# 3V3-CAN-Unisolated.net
KiCad netlist of a schematic drawn in Altium Designer
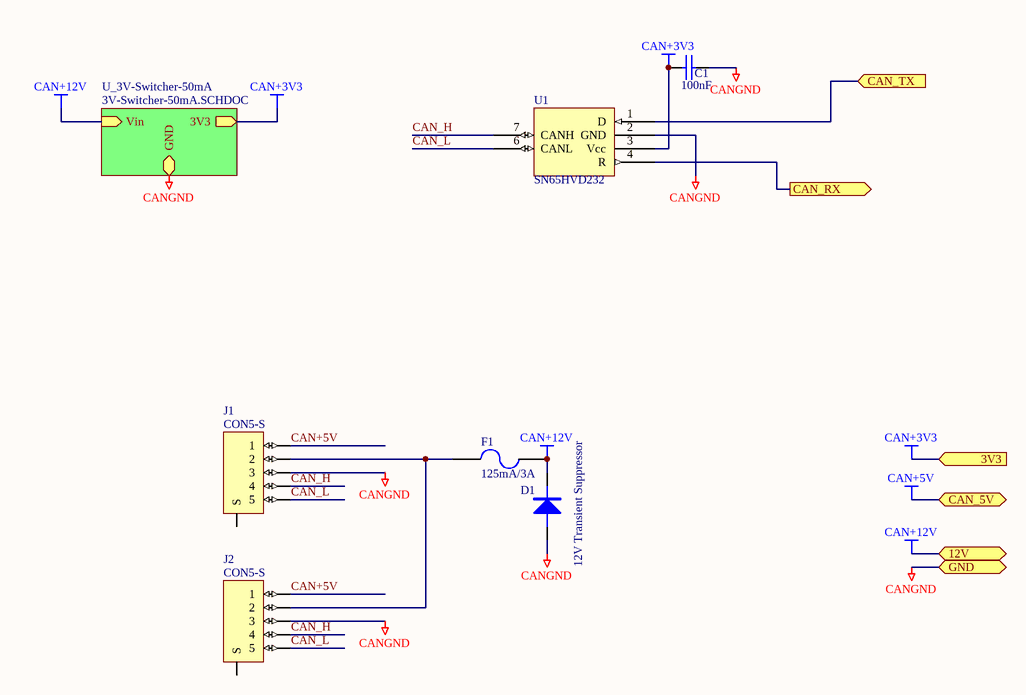
[diagram p0: 3V3-CAN-Unisolated.SchDoc]

(export (version "E")
  (design (tool "Eeschema 10.0.6"))
  (components
    (comp (ref "C1")
      (value "100nF")
      (footprint "0603")
      (description "Capacitor")
      (libsource (lib "*") (part "CAP"))
    )
    (comp (ref "D1")
      (value "12V Transient Suppressor")
      (footprint "SMA")
      (description "Diode")
      (libsource (lib "RCLDQ") (part "DIODE"))
    )
    (comp (ref "F1")
      (value "125mA/3A")
      (footprint "LITTELFUSE-154")
      (description "Fuse")
      (libsource (lib "*") (part "FUSE2"))
    )
    (comp (ref "J1")
      (value "CON5-S")
      (footprint "TRIAD5F")
      (description "Connector, 2 pin, with shield @ S")
      (libsource (lib "*") (part "CON5-S"))
    )
    (comp (ref "J2")
      (value "CON5-S")
      (footprint "TRIAD5F")
      (description "Connector, 2 pin, with shield @ S")
      (libsource (lib "*") (part "CON5-S"))
    )
    (comp (ref "U1")
      (value "SN65HVD232")
      (footprint "SO8")
      (description "3.3V CAN Transciever")
      (libsource (lib "*") (part "SN65HVD232"))
    )
  )
  (nets
    (net (code "1") (name "/CAN_H") (class "Default")
      (node (ref "J1") (pin "4") (pinfunction "4_4") (pintype "bidirectional"))
      (node (ref "J2") (pin "4") (pinfunction "4_4") (pintype "bidirectional"))
      (node (ref "U1") (pin "7") (pinfunction "CANH_7") (pintype "bidirectional"))
    )
    (net (code "2") (name "/CAN_L") (class "Default")
      (node (ref "J1") (pin "5") (pinfunction "5_5") (pintype "bidirectional"))
      (node (ref "J2") (pin "5") (pinfunction "5_5") (pintype "bidirectional"))
      (node (ref "U1") (pin "6") (pinfunction "CANL_6") (pintype "bidirectional"))
    )
    (net (code "3") (name "/CAN_RX") (class "Default")
      (node (ref "U1") (pin "4") (pinfunction "R_4") (pintype "output"))
    )
    (net (code "4") (name "/CAN_TX") (class "Default")
      (node (ref "U1") (pin "1") (pinfunction "D_1") (pintype "input"))
    )
    (net (code "5") (name "CAN+3V3") (class "Default")
      (node (ref "C1") (pin "2") (pinfunction "2_2") (pintype "passive"))
      (node (ref "U1") (pin "3") (pinfunction "Vcc_3") (pintype "power_in"))
    )
    (net (code "6") (name "CAN+5V") (class "Default")
      (node (ref "J1") (pin "1") (pinfunction "1_1") (pintype "bidirectional"))
      (node (ref "J2") (pin "1") (pinfunction "1_1") (pintype "bidirectional"))
    )
    (net (code "7") (name "CAN+12V") (class "Default")
      (node (ref "D1") (pin "K") (pinfunction "K_K") (pintype "passive"))
      (node (ref "F1") (pin "2") (pinfunction "2_2") (pintype "passive"))
    )
    (net (code "8") (name "CANGND") (class "Default")
      (node (ref "C1") (pin "1") (pinfunction "1_1") (pintype "passive"))
      (node (ref "D1") (pin "A") (pinfunction "A_A") (pintype "passive"))
      (node (ref "J1") (pin "3") (pinfunction "3_3") (pintype "bidirectional"))
      (node (ref "J2") (pin "3") (pinfunction "3_3") (pintype "bidirectional"))
      (node (ref "U1") (pin "2") (pinfunction "GND_2") (pintype "power_in"))
    )
    (net (code "9") (name "Net-(F1-Pad1)") (class "Default")
      (node (ref "F1") (pin "1") (pinfunction "1_1") (pintype "passive"))
      (node (ref "J1") (pin "2") (pinfunction "2_2") (pintype "bidirectional"))
      (node (ref "J2") (pin "2") (pinfunction "2_2") (pintype "bidirectional"))
    )
    (net (code "10") (name "unconnected-(J1-S-Pad0)") (class "Default")
      (node (ref "J1") (pin "0") (pinfunction "S_0") (pintype "bidirectional"))
    )
    (net (code "11") (name "unconnected-(J2-S-Pad0)") (class "Default")
      (node (ref "J2") (pin "0") (pinfunction "S_0") (pintype "bidirectional"))
    )
  )
)
